# LCD.net
KiCad netlist of a schematic drawn in Altium Designer
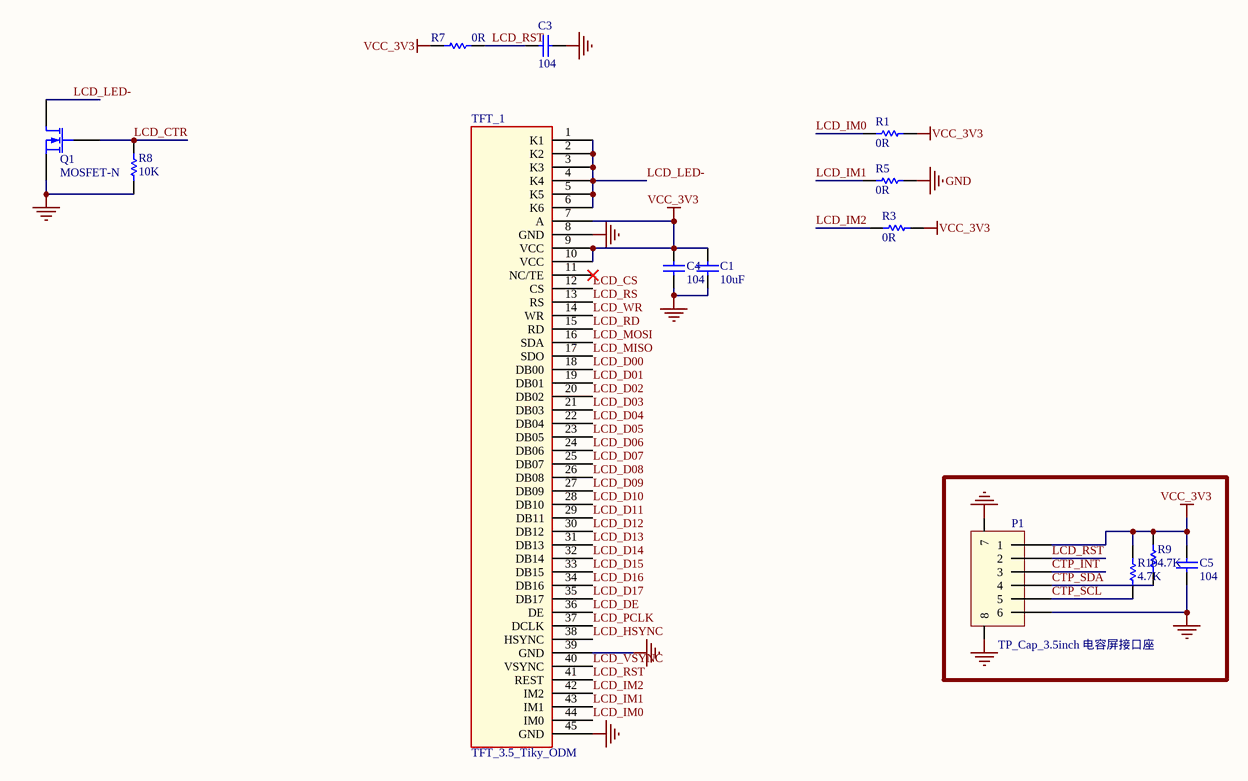
[diagram p0: LCD.SchDoc]

(export (version "E")
  (design (tool "Eeschema 10.0.6"))
  (components
    (comp (ref "C1")
      (value "10uF")
      (footprint "C 0603")
      (description "Capacitor")
      (libsource (lib "Miscellaneous Devices") (part "Cap"))
    )
    (comp (ref "C3") (value "104") (footprint "C 0603") (libsource (lib "Sheet") (part "CAP")))
    (comp (ref "C4")
      (value "104")
      (footprint "C 0603")
      (description "Capacitor")
      (libsource (lib "Miscellaneous Devices") (part "Cap"))
    )
    (comp (ref "C5")
      (value "104")
      (footprint "C 0603")
      (description "Capacitor")
      (libsource (lib "Miscellaneous Devices") (part "Cap"))
    )
    (comp (ref "P1")
      (value "TP_Cap_3.5inch 电容屏接口座")
      (footprint "TP_Cap_3.5inch")
      (libsource (lib "Tiky") (part "BHEADSMD1x6"))
    )
    (comp (ref "Q1") (value "MOSFET-N") (footprint "SOT-23") (libsource (lib "Tiky") (part "MOSFET-N")))
    (comp (ref "R1") (value "0R") (footprint "R 0603") (libsource (lib "Sheet") (part "RES")))
    (comp (ref "R3") (value "0R") (footprint "R 0603") (libsource (lib "Sheet") (part "RES")))
    (comp (ref "R5") (value "0R") (footprint "R 0603") (libsource (lib "Sheet") (part "RES")))
    (comp (ref "R7") (value "0R") (footprint "R 0603") (libsource (lib "Sheet") (part "RES")))
    (comp (ref "R8") (value "10K") (footprint "R 0603") (libsource (lib "Sheet") (part "RES")))
    (comp (ref "R9") (value "4.7K") (footprint "R 0603") (libsource (lib "Sheet") (part "RES")))
    (comp (ref "R10") (value "4.7K") (footprint "R 0603") (libsource (lib "Sheet") (part "RES")))
    (comp (ref "TFT_1")
      (value "TFT_3.5_Tiky_ODM")
      (footprint "TFT_3.5_TIKY_ODM")
      (libsource (lib "Tiky") (part "TFT_3.5_Tiky_ODM"))
    )
  )
  (nets
    (net (code "1") (name "/CTP_INT") (class "Default")
      (node (ref "P1") (pin "3") (pinfunction "3_3") (pintype "passive"))
    )
    (net (code "2") (name "/CTP_SCL") (class "Default")
      (node (ref "P1") (pin "5") (pinfunction "5_5") (pintype "passive"))
      (node (ref "R10") (pin "1") (pinfunction "1_1") (pintype "passive"))
    )
    (net (code "3") (name "/CTP_SDA") (class "Default")
      (node (ref "P1") (pin "4") (pinfunction "4_4") (pintype "passive"))
      (node (ref "R9") (pin "1") (pinfunction "1_1") (pintype "passive"))
    )
    (net (code "4") (name "/LCD_CS") (class "Default")
      (node (ref "TFT_1") (pin "12") (pinfunction "CS_12") (pintype "passive"))
    )
    (net (code "5") (name "/LCD_CTR") (class "Default")
      (node (ref "Q1") (pin "1") (pinfunction "G_1") (pintype "passive"))
      (node (ref "R8") (pin "1") (pinfunction "1_1") (pintype "passive"))
    )
    (net (code "6") (name "/LCD_D00") (class "Default")
      (node (ref "TFT_1") (pin "18") (pinfunction "DB00_18") (pintype "passive"))
    )
    (net (code "7") (name "/LCD_D01") (class "Default")
      (node (ref "TFT_1") (pin "19") (pinfunction "DB01_19") (pintype "passive"))
    )
    (net (code "8") (name "/LCD_D02") (class "Default")
      (node (ref "TFT_1") (pin "20") (pinfunction "DB02_20") (pintype "passive"))
    )
    (net (code "9") (name "/LCD_D03") (class "Default")
      (node (ref "TFT_1") (pin "21") (pinfunction "DB03_21") (pintype "passive"))
    )
    (net (code "10") (name "/LCD_D04") (class "Default")
      (node (ref "TFT_1") (pin "22") (pinfunction "DB04_22") (pintype "passive"))
    )
    (net (code "11") (name "/LCD_D05") (class "Default")
      (node (ref "TFT_1") (pin "23") (pinfunction "DB05_23") (pintype "passive"))
    )
    (net (code "12") (name "/LCD_D06") (class "Default")
      (node (ref "TFT_1") (pin "24") (pinfunction "DB06_24") (pintype "passive"))
    )
    (net (code "13") (name "/LCD_D07") (class "Default")
      (node (ref "TFT_1") (pin "25") (pinfunction "DB07_25") (pintype "passive"))
    )
    (net (code "14") (name "/LCD_D08") (class "Default")
      (node (ref "TFT_1") (pin "26") (pinfunction "DB08_26") (pintype "passive"))
    )
    (net (code "15") (name "/LCD_D09") (class "Default")
      (node (ref "TFT_1") (pin "27") (pinfunction "DB09_27") (pintype "passive"))
    )
    (net (code "16") (name "/LCD_D10") (class "Default")
      (node (ref "TFT_1") (pin "28") (pinfunction "DB10_28") (pintype "passive"))
    )
    (net (code "17") (name "/LCD_D11") (class "Default")
      (node (ref "TFT_1") (pin "29") (pinfunction "DB11_29") (pintype "passive"))
    )
    (net (code "18") (name "/LCD_D12") (class "Default")
      (node (ref "TFT_1") (pin "30") (pinfunction "DB12_30") (pintype "passive"))
    )
    (net (code "19") (name "/LCD_D13") (class "Default")
      (node (ref "TFT_1") (pin "31") (pinfunction "DB13_31") (pintype "passive"))
    )
    (net (code "20") (name "/LCD_D14") (class "Default")
      (node (ref "TFT_1") (pin "32") (pinfunction "DB14_32") (pintype "passive"))
    )
    (net (code "21") (name "/LCD_D15") (class "Default")
      (node (ref "TFT_1") (pin "33") (pinfunction "DB15_33") (pintype "passive"))
    )
    (net (code "22") (name "/LCD_D16") (class "Default")
      (node (ref "TFT_1") (pin "34") (pinfunction "DB16_34") (pintype "passive"))
    )
    (net (code "23") (name "/LCD_D17") (class "Default")
      (node (ref "TFT_1") (pin "35") (pinfunction "DB17_35") (pintype "passive"))
    )
    (net (code "24") (name "/LCD_DE") (class "Default")
      (node (ref "TFT_1") (pin "36") (pinfunction "DE_36") (pintype "passive"))
    )
    (net (code "25") (name "/LCD_HSYNC") (class "Default")
      (node (ref "TFT_1") (pin "38") (pinfunction "HSYNC_38") (pintype "passive"))
    )
    (net (code "26") (name "/LCD_IM0") (class "Default")
      (node (ref "R1") (pin "1") (pinfunction "1_1") (pintype "passive"))
      (node (ref "TFT_1") (pin "44") (pinfunction "IM0_44") (pintype "passive"))
    )
    (net (code "27") (name "/LCD_IM1") (class "Default")
      (node (ref "R5") (pin "1") (pinfunction "1_1") (pintype "passive"))
      (node (ref "TFT_1") (pin "43") (pinfunction "IM1_43") (pintype "passive"))
    )
    (net (code "28") (name "/LCD_IM2") (class "Default")
      (node (ref "R3") (pin "1") (pinfunction "1_1") (pintype "passive"))
      (node (ref "TFT_1") (pin "42") (pinfunction "IM2_42") (pintype "passive"))
    )
    (net (code "29") (name "/LCD_LED-") (class "Default")
      (node (ref "Q1") (pin "3") (pinfunction "D_3") (pintype "passive"))
      (node (ref "TFT_1") (pin "1") (pinfunction "K1_1") (pintype "passive"))
      (node (ref "TFT_1") (pin "2") (pinfunction "K2_2") (pintype "passive"))
      (node (ref "TFT_1") (pin "3") (pinfunction "K3_3") (pintype "passive"))
      (node (ref "TFT_1") (pin "4") (pinfunction "K4_4") (pintype "passive"))
      (node (ref "TFT_1") (pin "5") (pinfunction "K5_5") (pintype "passive"))
      (node (ref "TFT_1") (pin "6") (pinfunction "K6_6") (pintype "passive"))
    )
    (net (code "30") (name "/LCD_MISO") (class "Default")
      (node (ref "TFT_1") (pin "17") (pinfunction "SDO_17") (pintype "passive"))
    )
    (net (code "31") (name "/LCD_MOSI") (class "Default")
      (node (ref "TFT_1") (pin "16") (pinfunction "SDA_16") (pintype "passive"))
    )
    (net (code "32") (name "/LCD_PCLK") (class "Default")
      (node (ref "TFT_1") (pin "37") (pinfunction "DCLK_37") (pintype "passive"))
    )
    (net (code "33") (name "/LCD_RD") (class "Default")
      (node (ref "TFT_1") (pin "15") (pinfunction "RD_15") (pintype "passive"))
    )
    (net (code "34") (name "/LCD_RS") (class "Default")
      (node (ref "TFT_1") (pin "13") (pinfunction "RS_13") (pintype "passive"))
    )
    (net (code "35") (name "/LCD_RST") (class "Default")
      (node (ref "C3") (pin "2") (pinfunction "2_2") (pintype "passive"))
      (node (ref "P1") (pin "2") (pinfunction "2_2") (pintype "passive"))
      (node (ref "R7") (pin "2") (pinfunction "2_2") (pintype "passive"))
      (node (ref "TFT_1") (pin "41") (pinfunction "REST_41") (pintype "passive"))
    )
    (net (code "36") (name "/LCD_VSYNC") (class "Default")
      (node (ref "TFT_1") (pin "40") (pinfunction "VSYNC_40") (pintype "passive"))
    )
    (net (code "37") (name "/LCD_WR") (class "Default")
      (node (ref "TFT_1") (pin "14") (pinfunction "WR_14") (pintype "passive"))
    )
    (net (code "38") (name "GND") (class "Default")
      (node (ref "C1") (pin "2") (pinfunction "2_2") (pintype "passive"))
      (node (ref "C3") (pin "1") (pinfunction "1_1") (pintype "passive"))
      (node (ref "C4") (pin "2") (pinfunction "2_2") (pintype "passive"))
      (node (ref "C5") (pin "2") (pinfunction "2_2") (pintype "passive"))
      (node (ref "P1") (pin "6") (pinfunction "6_6") (pintype "passive"))
      (node (ref "P1") (pin "7") (pinfunction "7_7") (pintype "passive"))
      (node (ref "P1") (pin "8") (pinfunction "8_8") (pintype "passive"))
      (node (ref "Q1") (pin "2") (pinfunction "S_2") (pintype "passive"))
      (node (ref "R5") (pin "2") (pinfunction "2_2") (pintype "passive"))
      (node (ref "R8") (pin "2") (pinfunction "2_2") (pintype "passive"))
      (node (ref "TFT_1") (pin "39") (pinfunction "GND_39") (pintype "passive"))
      (node (ref "TFT_1") (pin "45") (pinfunction "GND_45") (pintype "passive"))
      (node (ref "TFT_1") (pin "8") (pinfunction "GND_8") (pintype "passive"))
    )
    (net (code "39") (name "VCC_3V3") (class "Default")
      (node (ref "C1") (pin "1") (pinfunction "1_1") (pintype "passive"))
      (node (ref "C4") (pin "1") (pinfunction "1_1") (pintype "passive"))
      (node (ref "C5") (pin "1") (pinfunction "1_1") (pintype "passive"))
      (node (ref "P1") (pin "1") (pinfunction "1_1") (pintype "passive"))
      (node (ref "R1") (pin "2") (pinfunction "2_2") (pintype "passive"))
      (node (ref "R10") (pin "2") (pinfunction "2_2") (pintype "passive"))
      (node (ref "R3") (pin "2") (pinfunction "2_2") (pintype "passive"))
      (node (ref "R7") (pin "1") (pinfunction "1_1") (pintype "passive"))
      (node (ref "R9") (pin "2") (pinfunction "2_2") (pintype "passive"))
      (node (ref "TFT_1") (pin "10") (pinfunction "VCC_10") (pintype "passive"))
      (node (ref "TFT_1") (pin "7") (pinfunction "A_7") (pintype "passive"))
      (node (ref "TFT_1") (pin "9") (pinfunction "VCC_9") (pintype "passive"))
    )
    (net (code "40") (name "unconnected-(TFT_1-NC{slash}TE-Pad11)") (class "Default")
      (node (ref "TFT_1") (pin "11") (pinfunction "NC/TE_11") (pintype "passive+no_connect"))
    )
  )
)
